# working.net
KiCad netlist of a schematic drawn in EAGLE
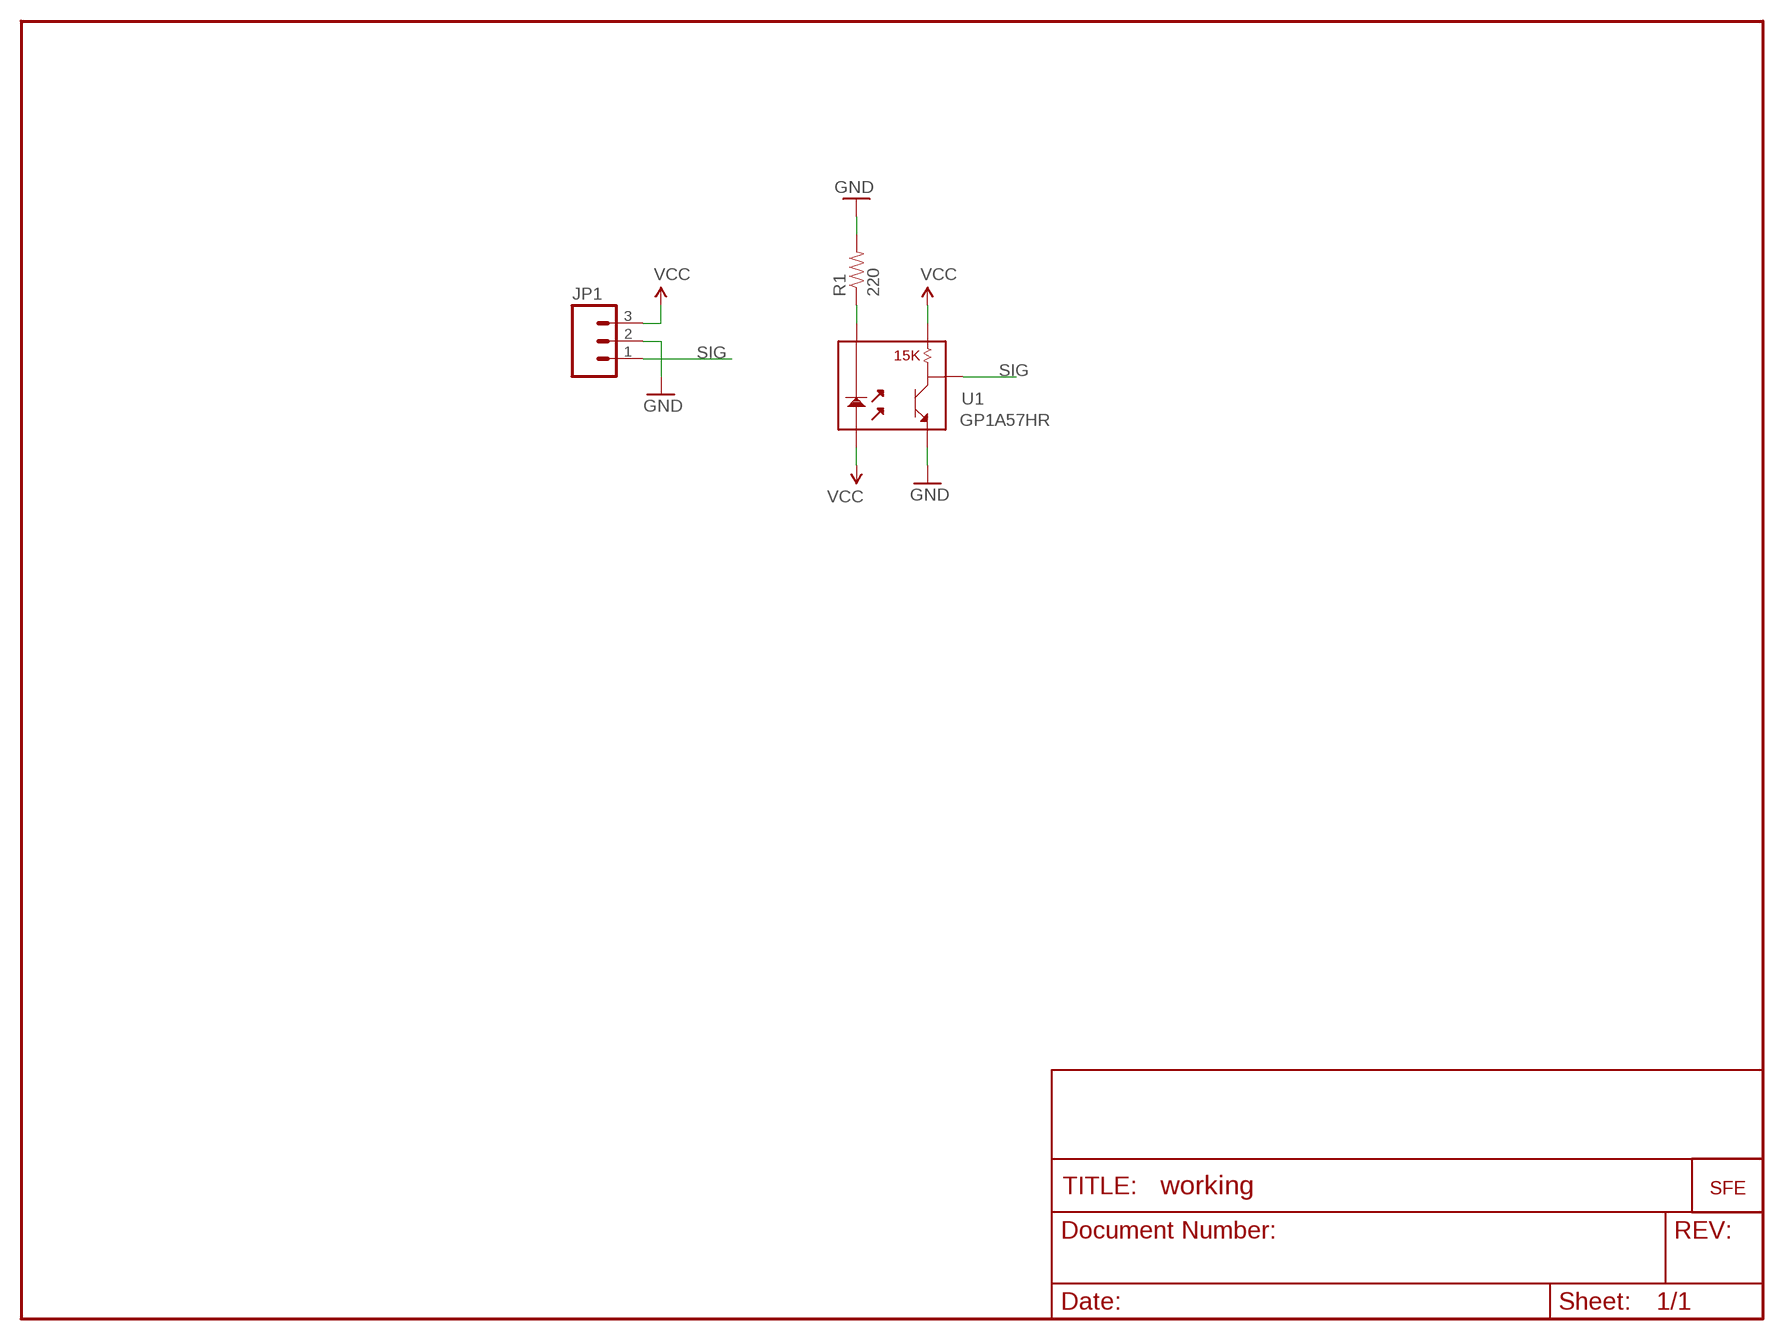
[diagram p0: schematic, sheet 1]

(export (version "E")
  (design (tool "Eeschema 10.0.6"))
  (components
    (comp (ref "JP1")
      (value "M03PTH")
      (footprint "eagle-import:1X03")
      (libsource (lib "eagle-import") (part "M03PTH"))
    )
    (comp (ref "R1")
      (value "220")
      (footprint "eagle-import:AXIAL-0.3")
      (libsource (lib "eagle-import") (part "RESISTORPTH1"))
    )
    (comp (ref "U1")
      (value "GP1A57HR")
      (footprint "eagle-import:GP1A57HR")
      (libsource (lib "eagle-import") (part "GP1A57HR"))
    )
    (comp (ref "U2")
      (value "LOGO-SFESK")
      (footprint "eagle-import:SFE-LOGO-FLAME")
      (libsource (lib "eagle-import") (part "LOGO-SFESK"))
    )
  )
  (nets
    (net (code "1") (name "/SIG") (class "Default")
      (node (ref "JP1") (pin "1") (pinfunction "1_1") (pintype "passive"))
      (node (ref "U1") (pin "4") (pinfunction "4_4") (pintype "bidirectional"))
    )
    (net (code "2") (name "GND") (class "Default")
      (node (ref "JP1") (pin "2") (pinfunction "2_2") (pintype "passive"))
      (node (ref "R1") (pin "P$2") (pinfunction "2_P$2") (pintype "passive"))
      (node (ref "U1") (pin "5") (pinfunction "5_5") (pintype "bidirectional"))
    )
    (net (code "3") (name "Net-(R1-1)") (class "Default")
      (node (ref "R1") (pin "P$1") (pinfunction "1_P$1") (pintype "passive"))
      (node (ref "U1") (pin "2") (pinfunction "2_2") (pintype "bidirectional"))
    )
    (net (code "4") (name "VCC") (class "Default")
      (node (ref "JP1") (pin "3") (pinfunction "3_3") (pintype "passive"))
      (node (ref "U1") (pin "1") (pinfunction "1_1") (pintype "bidirectional"))
      (node (ref "U1") (pin "3") (pinfunction "3_3") (pintype "bidirectional"))
    )
  )
)
